# SCH_USB-2_0-KVM-Switch-Hub_2026-04-15.net
KiCad netlist of a schematic drawn in EasyEDA
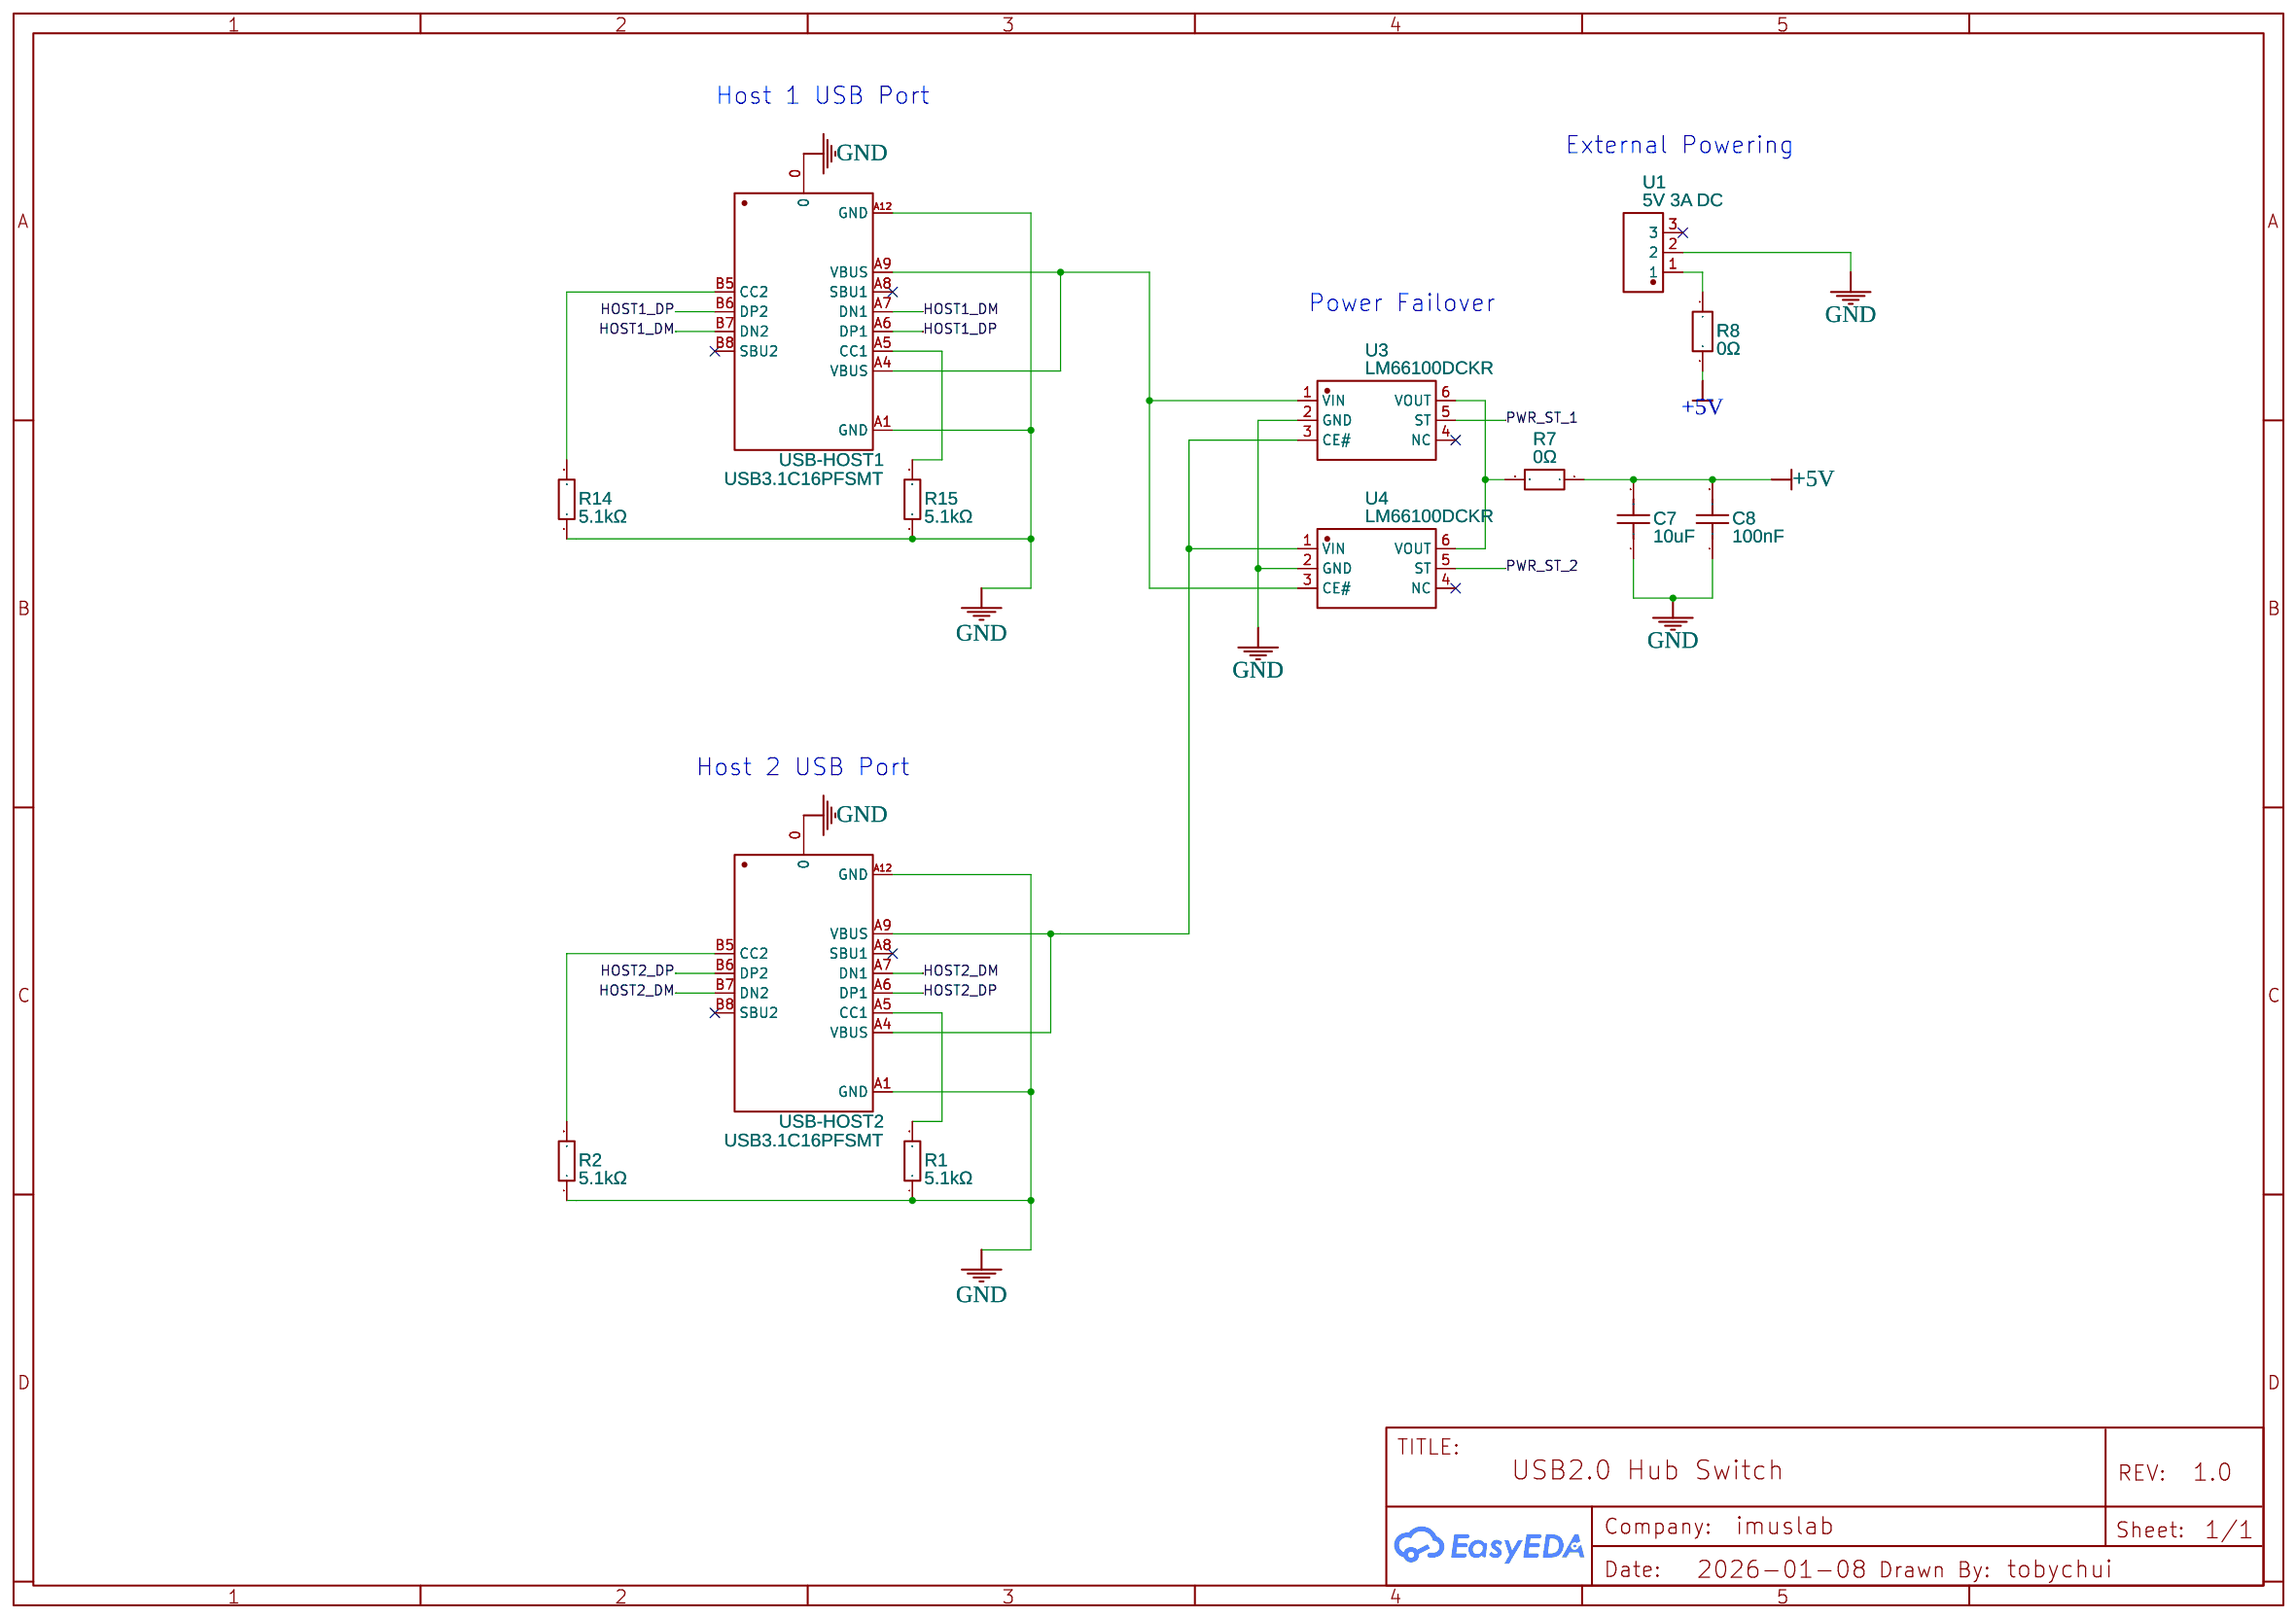
[diagram p0: hosts]
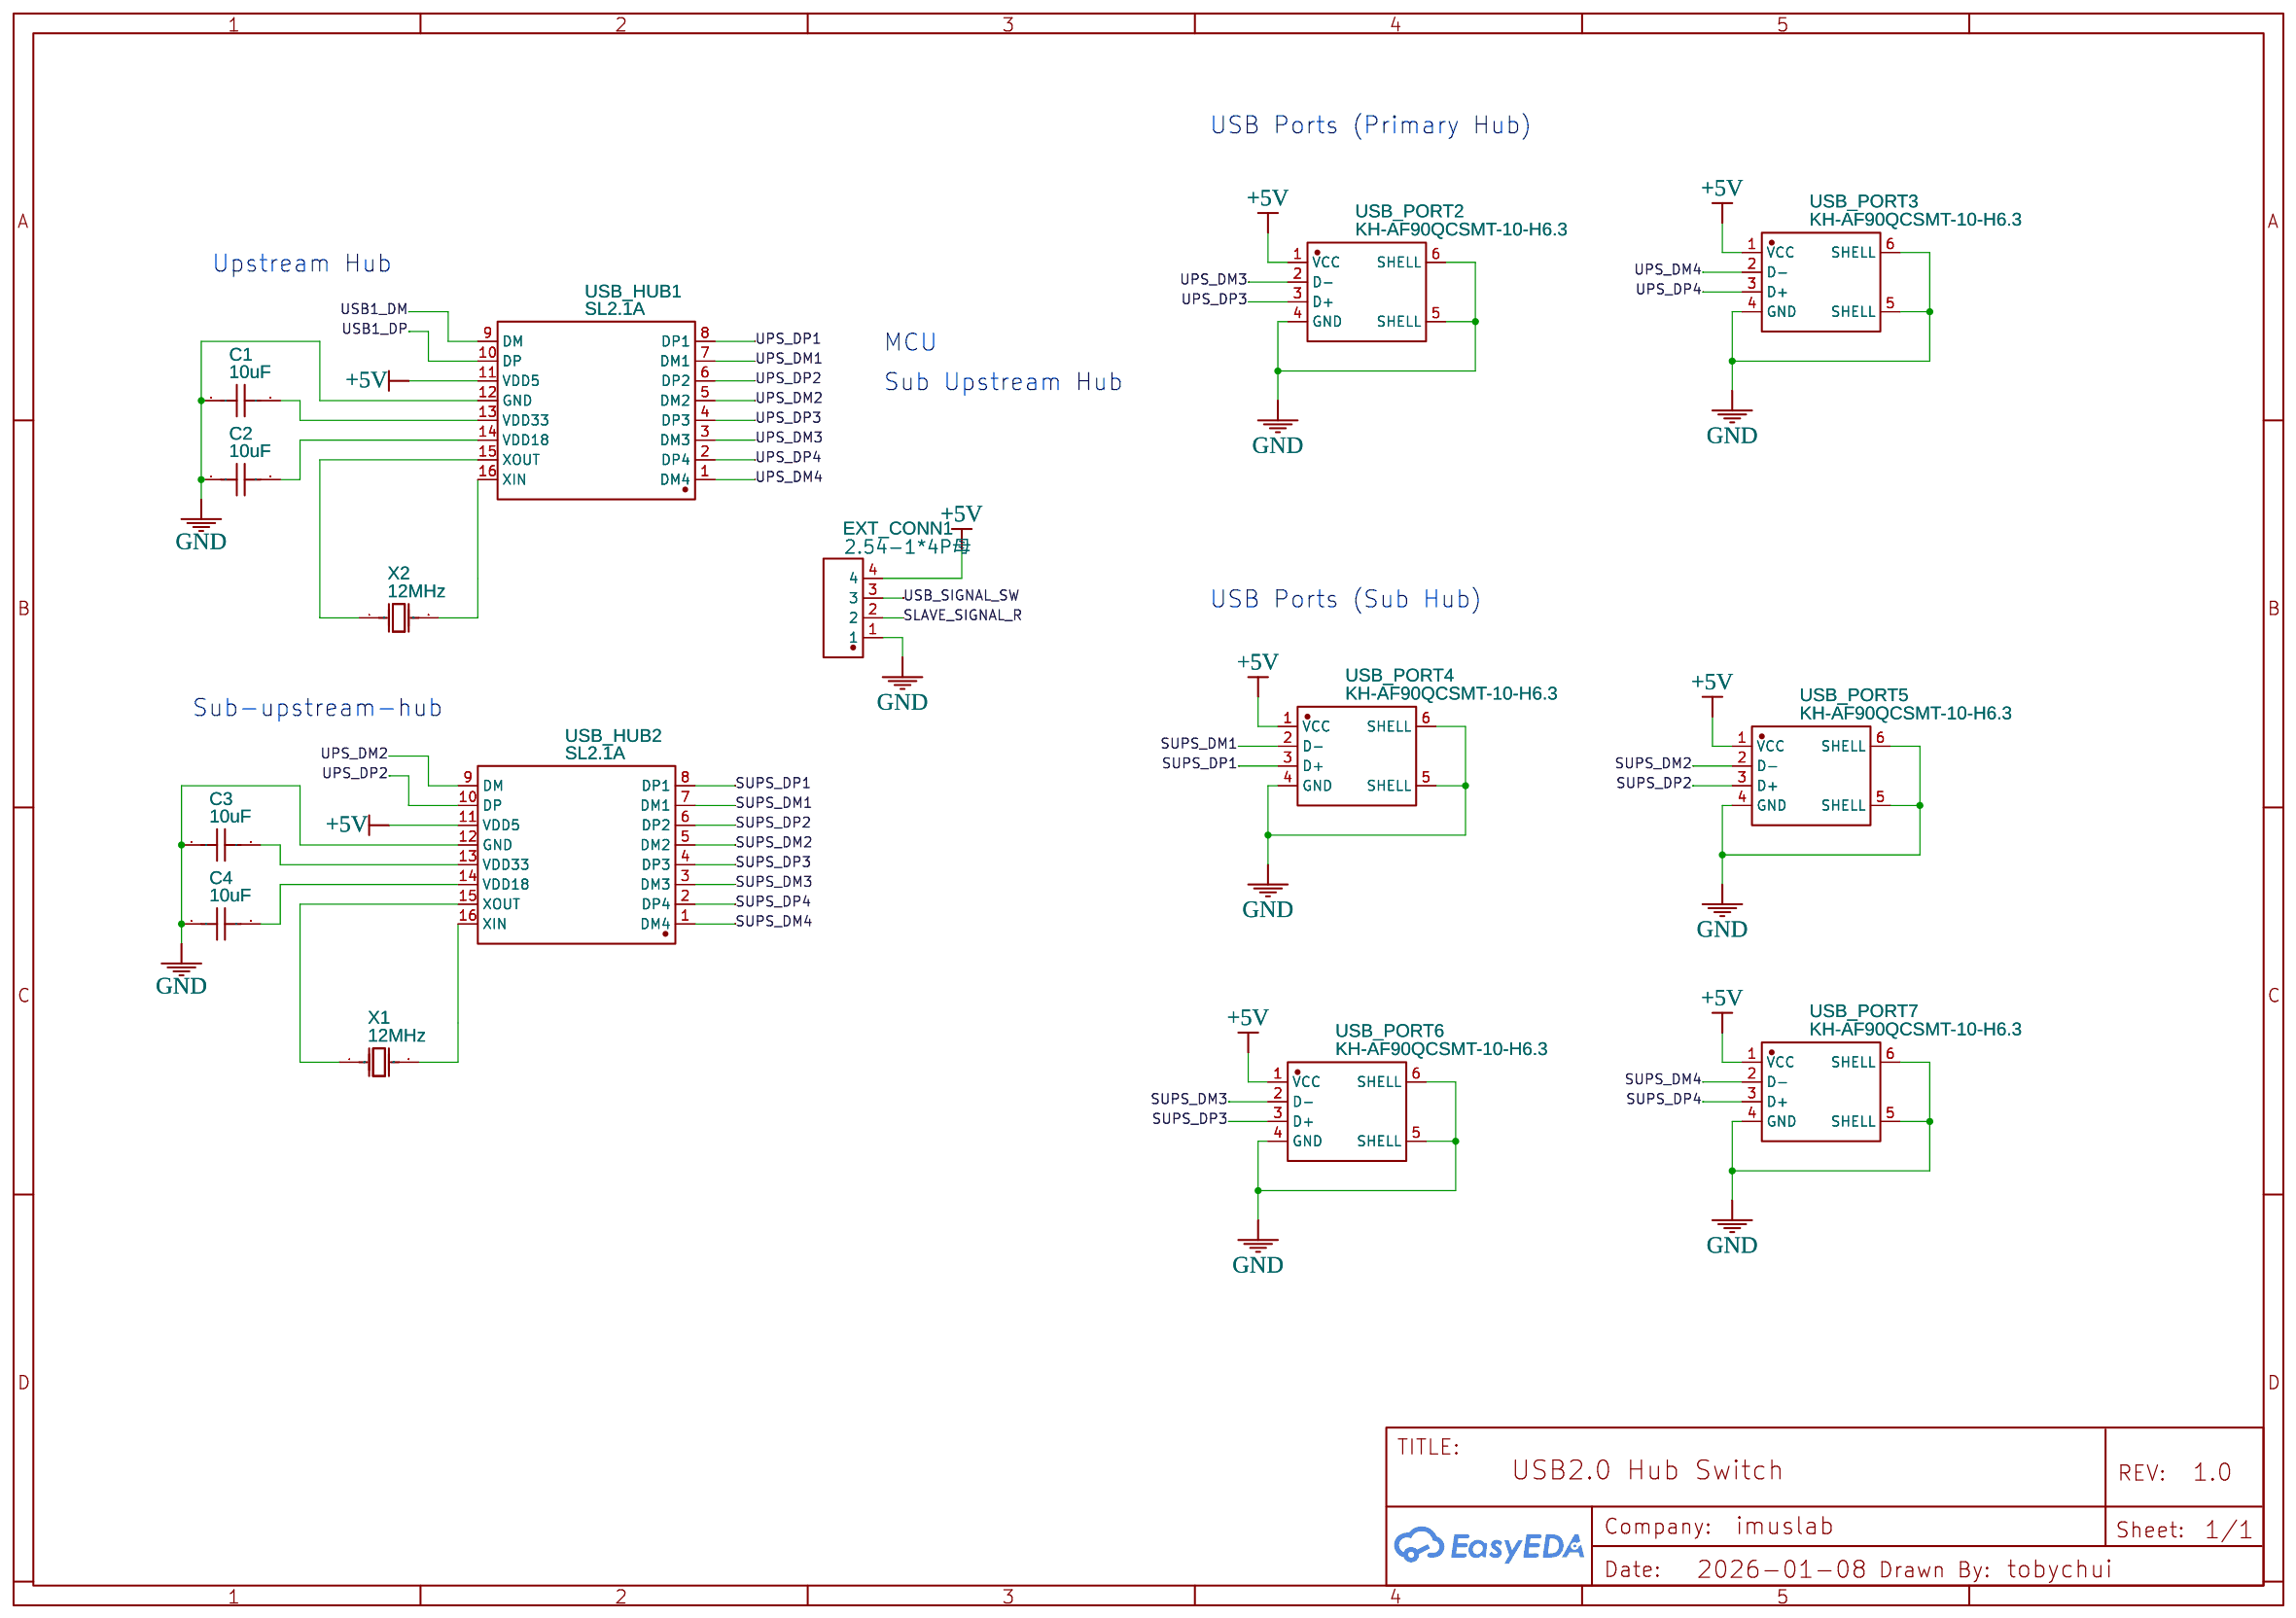
[diagram p1: usb]
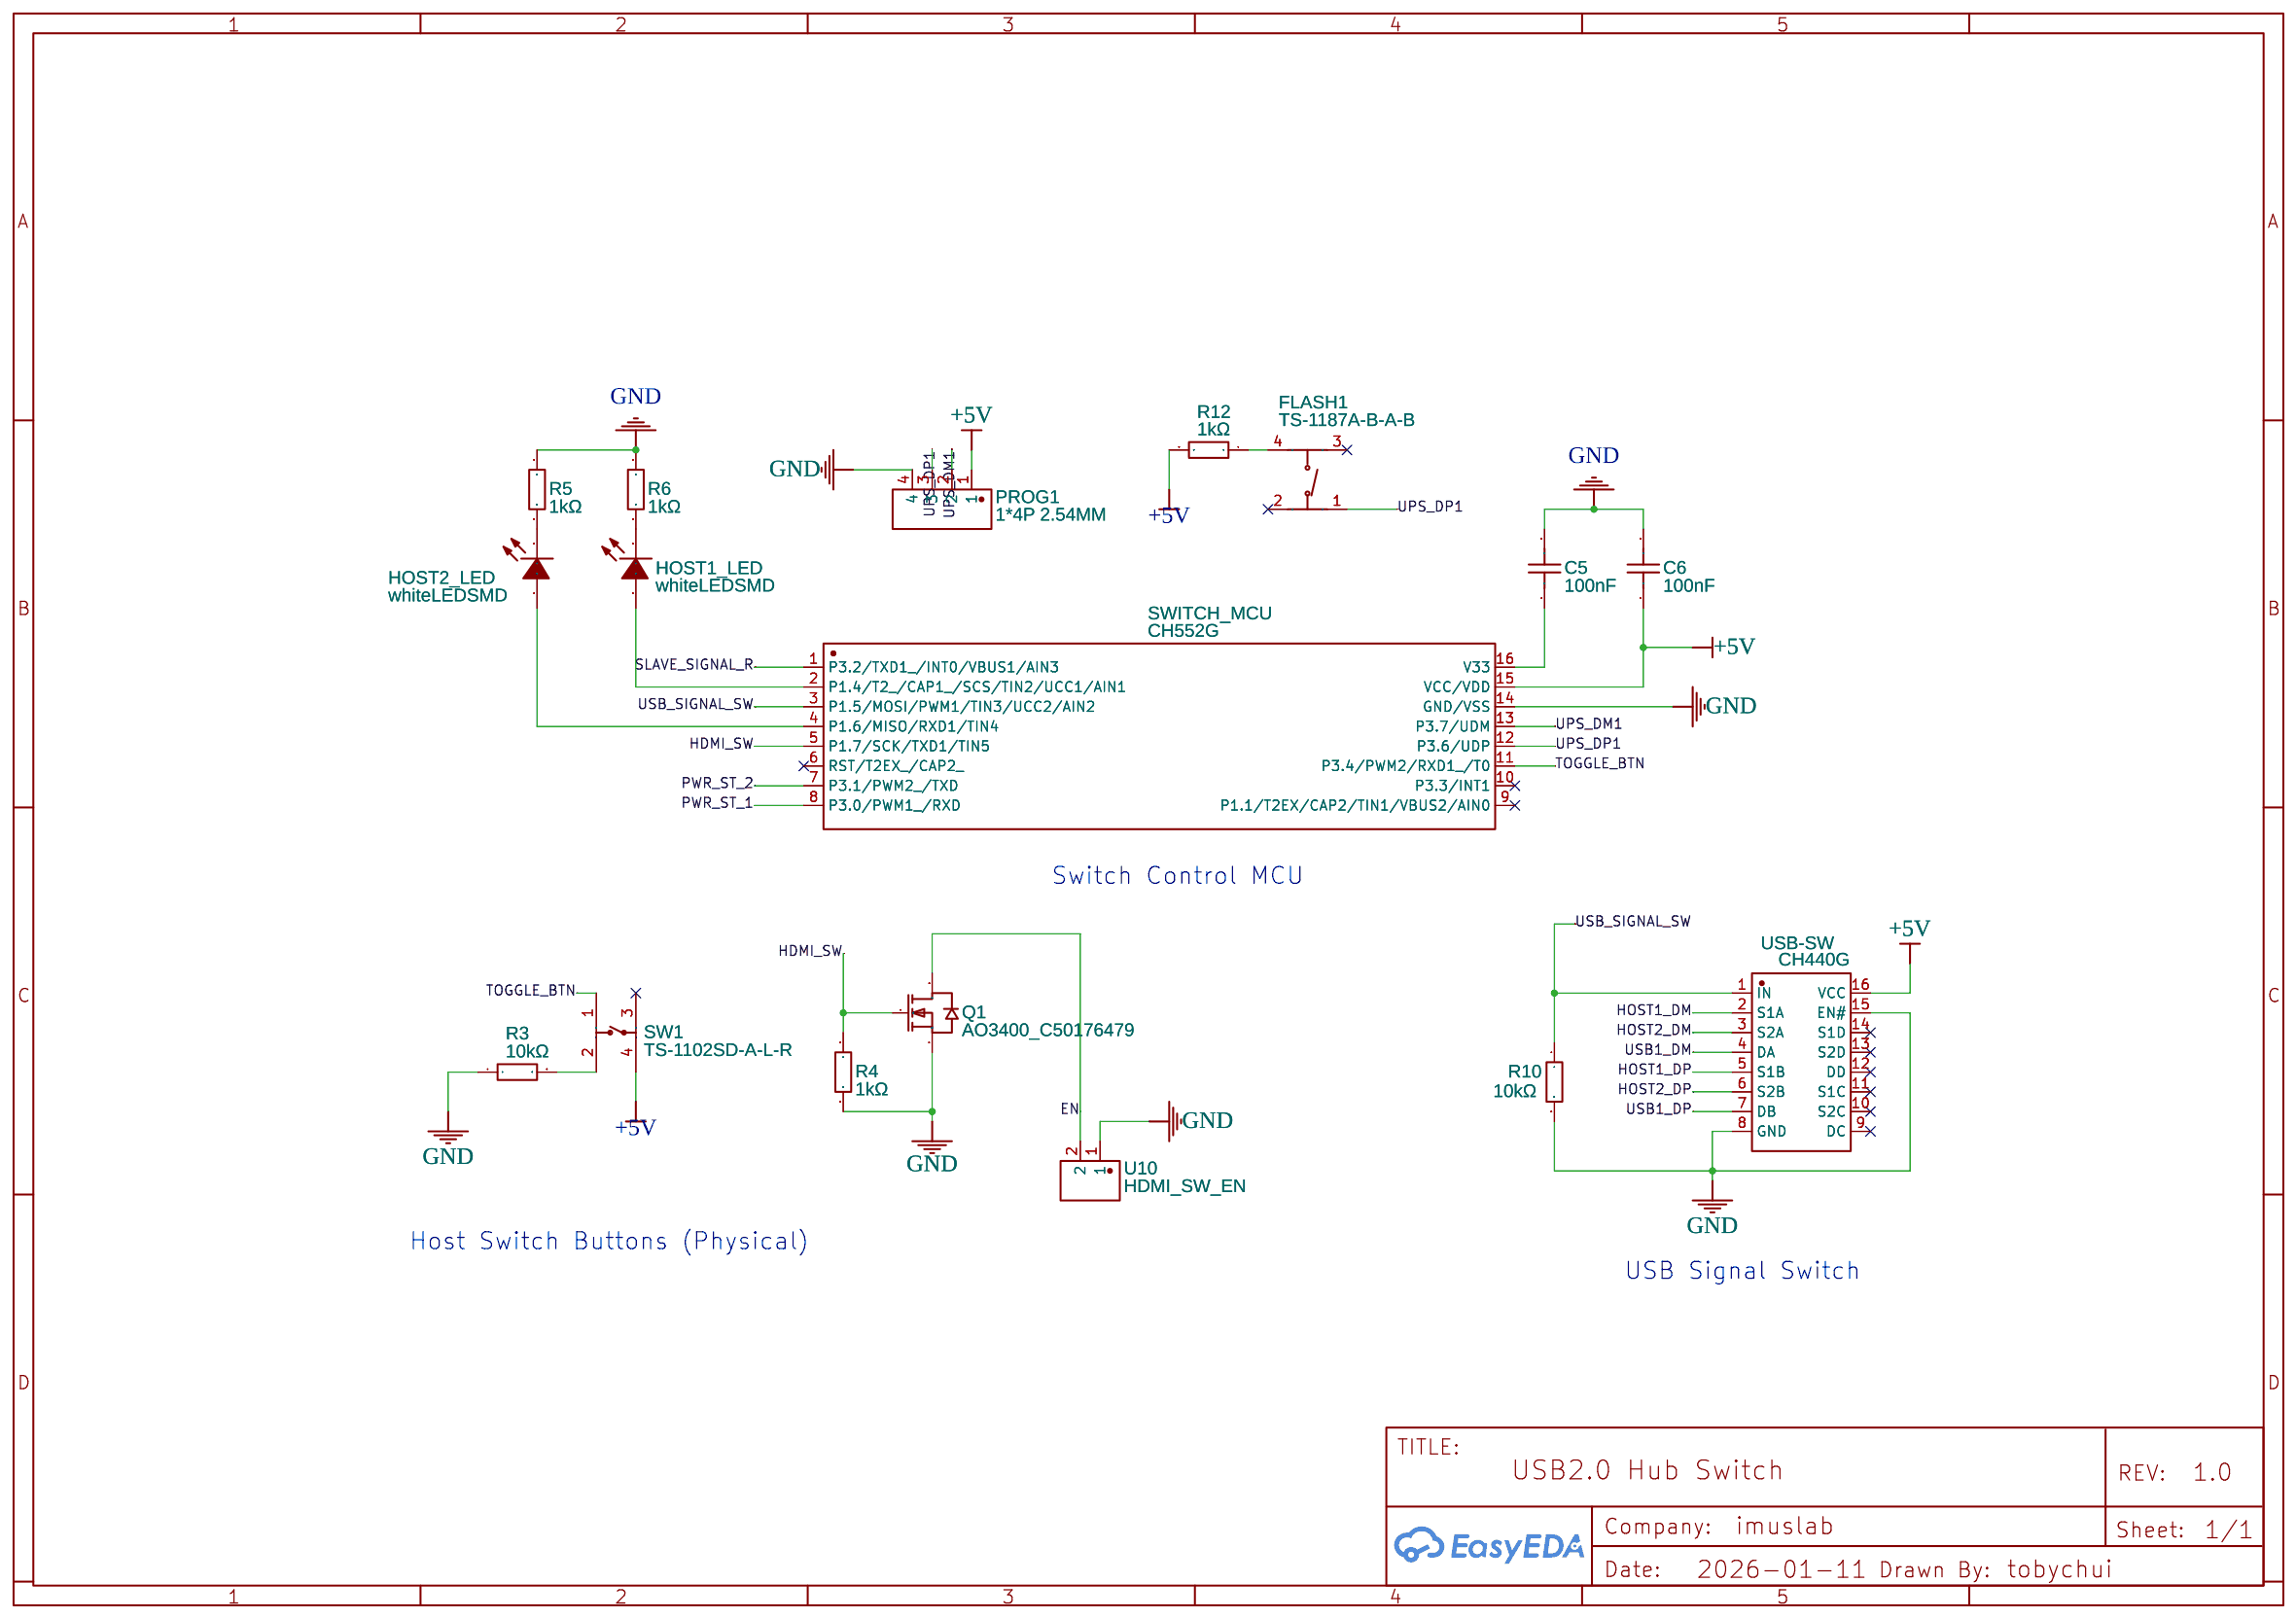
[diagram p2: Switching]

(export (version "E")
  (design (tool "Eeschema 10.0.6"))
  (components
    (comp (ref "C7")
      (value "10uF")
      (fields
        (field (name "Manufacturer Part") "CL21A106KAYNNNE")
        (field (name "Manufacturer") "SAMSUNG(三星)")
      )
      (libsource (lib "") (part "CL21A106KAYNNNE"))
    )
    (comp (ref "C8")
      (value "100nF")
      (fields
        (field (name "Manufacturer Part") "CC0805KRX7R9BB104")
        (field (name "Manufacturer") "YAGEO(国巨)")
      )
      (libsource (lib "") (part "CC0805KRX7R9BB104"))
    )
    (comp (ref "R1")
      (value "5.1kΩ")
      (fields
        (field (name "Manufacturer Part") "0805W8F5101T5E")
        (field (name "Manufacturer") "UNI-ROYAL(厚声)")
      )
      (libsource (lib "") (part "0805W8F5101T5E"))
    )
    (comp (ref "R2")
      (value "5.1kΩ")
      (fields
        (field (name "Manufacturer Part") "0805W8F5101T5E")
        (field (name "Manufacturer") "UNI-ROYAL(厚声)")
      )
      (libsource (lib "") (part "0805W8F5101T5E"))
    )
    (comp (ref "R7")
      (value "0Ω")
      (fields (field (name "Manufacturer Part") "YLRY05-W2-0Z") (field (name "Manufacturer") "yezhan(业展)"))
      (libsource (lib "") (part "YLRY05-W2-0Z_1"))
    )
    (comp (ref "R8")
      (value "0Ω")
      (fields (field (name "Manufacturer Part") "YLRY05-W2-0Z") (field (name "Manufacturer") "yezhan(业展)"))
      (libsource (lib "") (part "YLRY05-W2-0Z"))
    )
    (comp (ref "R14")
      (value "5.1kΩ")
      (fields
        (field (name "Manufacturer Part") "0805W8F5101T5E")
        (field (name "Manufacturer") "UNI-ROYAL(厚声)")
      )
      (libsource (lib "") (part "0805W8F5101T5E"))
    )
    (comp (ref "R15")
      (value "5.1kΩ")
      (fields
        (field (name "Manufacturer Part") "0805W8F5101T5E")
        (field (name "Manufacturer") "UNI-ROYAL(厚声)")
      )
      (libsource (lib "") (part "0805W8F5101T5E"))
    )
    (comp (ref "U1")
      (value "5V 3A DC")
      (fields (field (name "Manufacturer Part") "HC-DC-007B-2.5") (field (name "Manufacturer") "HCTL(华灿天禄)"))
      (libsource (lib "") (part "HC-DC-007B-2.5"))
    )
    (comp (ref "U3")
      (value "LM66100DCKR")
      (fields (field (name "Manufacturer") "TI(德州仪器)"))
      (libsource (lib "") (part "LM66100DCKR"))
    )
    (comp (ref "U4")
      (value "LM66100DCKR")
      (fields (field (name "Manufacturer") "TI(德州仪器)"))
      (libsource (lib "") (part "LM66100DCKR"))
    )
    (comp (ref "USB-HOST1")
      (value "USB3.1C16PFSMT")
      (fields (field (name "Manufacturer Part") "918-418K2023S40001") (field (name "Manufacturer") "精拓金"))
      (libsource (lib "") (part "USB3.1C16PFSMT"))
    )
    (comp (ref "USB-HOST2")
      (value "USB3.1C16PFSMT")
      (fields (field (name "Manufacturer Part") "918-418K2023S40001") (field (name "Manufacturer") "精拓金"))
      (libsource (lib "") (part "USB3.1C16PFSMT"))
    )
    (comp (ref "C1")
      (value "10uF")
      (fields
        (field (name "Manufacturer Part") "CL21A106KAYNNNE")
        (field (name "Manufacturer") "SAMSUNG(三星)")
      )
      (libsource (lib "") (part "CL21A106KAYNNNE"))
    )
    (comp (ref "C2")
      (value "10uF")
      (fields
        (field (name "Manufacturer Part") "CL21A106KAYNNNE")
        (field (name "Manufacturer") "SAMSUNG(三星)")
      )
      (libsource (lib "") (part "CL21A106KAYNNNE"))
    )
    (comp (ref "C3")
      (value "10uF")
      (fields
        (field (name "Manufacturer Part") "CL21A106KAYNNNE")
        (field (name "Manufacturer") "SAMSUNG(三星)")
      )
      (libsource (lib "") (part "CL21A106KAYNNNE"))
    )
    (comp (ref "C4")
      (value "10uF")
      (fields
        (field (name "Manufacturer Part") "CL21A106KAYNNNE")
        (field (name "Manufacturer") "SAMSUNG(三星)")
      )
      (libsource (lib "") (part "CL21A106KAYNNNE"))
    )
    (comp (ref "EXT_CONN1")
      (value "2.54-1*4P母")
      (fields (field (name "Manufacturer") "BOOMELE(博穆精密)"))
      (libsource (lib "") (part "2.54-1*4P母"))
    )
    (comp (ref "USB_HUB1")
      (value "SL2.1A")
      (fields (field (name "Manufacturer") "CoreChips(和芯润德)"))
      (libsource (lib "") (part "SL2.1A"))
    )
    (comp (ref "USB_HUB2")
      (value "SL2.1A")
      (fields (field (name "Manufacturer") "CoreChips(和芯润德)"))
      (libsource (lib "") (part "SL2.1A"))
    )
    (comp (ref "USB_PORT2")
      (value "KH-AF90QCSMT-10-H6.3")
      (fields (field (name "Manufacturer") "kinghelm(金航标)"))
      (libsource (lib "") (part "KH-AF90QCSMT-10-H6.3"))
    )
    (comp (ref "USB_PORT3")
      (value "KH-AF90QCSMT-10-H6.3")
      (fields (field (name "Manufacturer") "kinghelm(金航标)"))
      (libsource (lib "") (part "KH-AF90QCSMT-10-H6.3"))
    )
    (comp (ref "USB_PORT4")
      (value "KH-AF90QCSMT-10-H6.3")
      (fields (field (name "Manufacturer") "kinghelm(金航标)"))
      (libsource (lib "") (part "KH-AF90QCSMT-10-H6.3"))
    )
    (comp (ref "USB_PORT5")
      (value "KH-AF90QCSMT-10-H6.3")
      (fields (field (name "Manufacturer") "kinghelm(金航标)"))
      (libsource (lib "") (part "KH-AF90QCSMT-10-H6.3"))
    )
    (comp (ref "USB_PORT6")
      (value "KH-AF90QCSMT-10-H6.3")
      (fields (field (name "Manufacturer") "kinghelm(金航标)"))
      (libsource (lib "") (part "KH-AF90QCSMT-10-H6.3"))
    )
    (comp (ref "USB_PORT7")
      (value "KH-AF90QCSMT-10-H6.3")
      (fields (field (name "Manufacturer") "kinghelm(金航标)"))
      (libsource (lib "") (part "KH-AF90QCSMT-10-H6.3"))
    )
    (comp (ref "X1")
      (value "12MHz")
      (fields (field (name "Manufacturer Part") "X503212MSD2GI") (field (name "Manufacturer") "YXC(扬兴晶振)"))
      (libsource (lib "") (part "X503212MSD2GI"))
    )
    (comp (ref "X2")
      (value "12MHz")
      (fields (field (name "Manufacturer Part") "X503212MSD2GI") (field (name "Manufacturer") "YXC(扬兴晶振)"))
      (libsource (lib "") (part "X503212MSD2GI"))
    )
    (comp (ref "C5")
      (value "100nF")
      (fields
        (field (name "Manufacturer Part") "CC0805KRX7R9BB104")
        (field (name "Manufacturer") "YAGEO(国巨)")
      )
      (libsource (lib "") (part "CC0805KRX7R9BB104"))
    )
    (comp (ref "C6")
      (value "100nF")
      (fields
        (field (name "Manufacturer Part") "CC0805KRX7R9BB104")
        (field (name "Manufacturer") "YAGEO(国巨)")
      )
      (libsource (lib "") (part "CC0805KRX7R9BB104"))
    )
    (comp (ref "FLASH1")
      (value "TS-1187A-B-A-B")
      (fields (field (name "Manufacturer") "XKB Connectivity(中国星坤)"))
      (libsource (lib "") (part "TS-1187A-B-A-B"))
    )
    (comp (ref "HOST1_LED")
      (value "whiteLEDSMD")
      (fields (field (name "Manufacturer Part") "KT-0805W") (field (name "Manufacturer") "KENTO"))
      (libsource (lib "") (part "whiteLEDSMD"))
    )
    (comp (ref "HOST2_LED")
      (value "whiteLEDSMD")
      (fields (field (name "Manufacturer Part") "KT-0805W") (field (name "Manufacturer") "KENTO"))
      (libsource (lib "") (part "whiteLEDSMD_1"))
    )
    (comp (ref "PROG1")
      (value "1*4P 2.54MM")
      (fields (field (name "Manufacturer Part") "单排直插排针 1*4P 2.54mm"))
      (libsource (lib "") (part "1*4P 2.54MM"))
    )
    (comp (ref "Q1")
      (value "AO3400_C50176479")
      (fields (field (name "Manufacturer Part") "AO3400") (field (name "Manufacturer") "SEP(威旺)"))
      (libsource (lib "") (part "AO3400_C50176479"))
    )
    (comp (ref "R3")
      (value "10kΩ")
      (fields
        (field (name "Manufacturer Part") "0805W8F1002T5E")
        (field (name "Manufacturer") "UNI-ROYAL(厚声)")
      )
      (libsource (lib "") (part "0805W8F1002T5E_1"))
    )
    (comp (ref "R4")
      (value "1kΩ")
      (fields
        (field (name "Manufacturer Part") "0805W8F1001T5E")
        (field (name "Manufacturer") "UNI-ROYAL(厚声)")
      )
      (libsource (lib "") (part "0805W8F1001T5E"))
    )
    (comp (ref "R5")
      (value "1kΩ")
      (fields
        (field (name "Manufacturer Part") "0805W8F1001T5E")
        (field (name "Manufacturer") "UNI-ROYAL(厚声)")
      )
      (libsource (lib "") (part "0805W8F1001T5E"))
    )
    (comp (ref "R6")
      (value "1kΩ")
      (fields
        (field (name "Manufacturer Part") "0805W8F1001T5E")
        (field (name "Manufacturer") "UNI-ROYAL(厚声)")
      )
      (libsource (lib "") (part "0805W8F1001T5E"))
    )
    (comp (ref "R10")
      (value "10kΩ")
      (fields
        (field (name "Manufacturer Part") "0805W8F1002T5E")
        (field (name "Manufacturer") "UNI-ROYAL(厚声)")
      )
      (libsource (lib "") (part "0805W8F1002T5E"))
    )
    (comp (ref "R12")
      (value "1kΩ")
      (fields
        (field (name "Manufacturer Part") "0805W8F1001T5E")
        (field (name "Manufacturer") "UNI-ROYAL(厚声)")
      )
      (libsource (lib "") (part "0805W8F1001T5E_1"))
    )
    (comp (ref "SW1")
      (value "TS-1102SD-A-L-R")
      (fields (field (name "Manufacturer") "XKB Connection(中国星坤)"))
      (libsource (lib "") (part "TS-1102SD-A-L-R"))
    )
    (comp (ref "SWITCH_MCU")
      (value "CH552G")
      (fields (field (name "Manufacturer") "WCH(南京沁恒)"))
      (libsource (lib "") (part "CH552G"))
    )
    (comp (ref "U10")
      (value "HDMI_SW_EN")
      (fields
        (field (name "Manufacturer Part") "254PM-1x2P-V")
        (field (name "Manufacturer") "LXWCONN(连兴旺电子)")
      )
      (libsource (lib "") (part "254PM-1X2P-V"))
    )
    (comp (ref "USB-SW")
      (value "CH440G")
      (fields (field (name "Manufacturer") "WCH(南京沁恒)"))
      (libsource (lib "") (part "CH440G"))
    )
  )
  (nets
    (net (code "1") (name "+5V") (class "Default")
      (node (ref "C6") (pin "1") (pinfunction "1_1") (pintype "unspecified"))
      (node (ref "C7") (pin "2") (pinfunction "2_2") (pintype "unspecified"))
      (node (ref "C8") (pin "2") (pinfunction "2_2") (pintype "unspecified"))
      (node (ref "EXT_CONN1") (pin "4") (pinfunction "4_4") (pintype "unspecified"))
      (node (ref "PROG1") (pin "1") (pinfunction "1_1") (pintype "unspecified"))
      (node (ref "R12") (pin "2") (pinfunction "2_2") (pintype "input"))
      (node (ref "R7") (pin "1") (pinfunction "1_1") (pintype "unspecified"))
      (node (ref "R8") (pin "2") (pinfunction "2_2") (pintype "unspecified"))
      (node (ref "SW1") (pin "4") (pinfunction "4_4") (pintype "unspecified"))
      (node (ref "SWITCH_MCU") (pin "15") (pinfunction "VCC/VDD_15") (pintype "unspecified"))
      (node (ref "USB-SW") (pin "16") (pinfunction "VCC_16") (pintype "unspecified"))
      (node (ref "USB_HUB1") (pin "11") (pinfunction "VDD5_11") (pintype "unspecified"))
      (node (ref "USB_HUB2") (pin "11") (pinfunction "VDD5_11") (pintype "unspecified"))
      (node (ref "USB_PORT2") (pin "1") (pinfunction "VCC_1") (pintype "unspecified"))
      (node (ref "USB_PORT3") (pin "1") (pinfunction "VCC_1") (pintype "unspecified"))
      (node (ref "USB_PORT4") (pin "1") (pinfunction "VCC_1") (pintype "unspecified"))
      (node (ref "USB_PORT5") (pin "1") (pinfunction "VCC_1") (pintype "unspecified"))
      (node (ref "USB_PORT6") (pin "1") (pinfunction "VCC_1") (pintype "unspecified"))
      (node (ref "USB_PORT7") (pin "1") (pinfunction "VCC_1") (pintype "unspecified"))
    )
    (net (code "2") (name "EN") (class "Default")
      (node (ref "Q1") (pin "3") (pinfunction "D_3") (pintype "unspecified"))
      (node (ref "U10") (pin "2") (pinfunction "2_2") (pintype "unspecified"))
    )
    (net (code "3") (name "GND") (class "Default")
      (node (ref "C1") (pin "1") (pinfunction "1_1") (pintype "unspecified"))
      (node (ref "C2") (pin "1") (pinfunction "1_1") (pintype "unspecified"))
      (node (ref "C3") (pin "1") (pinfunction "1_1") (pintype "unspecified"))
      (node (ref "C4") (pin "1") (pinfunction "1_1") (pintype "unspecified"))
      (node (ref "C5") (pin "2") (pinfunction "2_2") (pintype "unspecified"))
      (node (ref "C6") (pin "2") (pinfunction "2_2") (pintype "unspecified"))
      (node (ref "C7") (pin "1") (pinfunction "1_1") (pintype "unspecified"))
      (node (ref "C8") (pin "1") (pinfunction "1_1") (pintype "unspecified"))
      (node (ref "EXT_CONN1") (pin "1") (pinfunction "1_1") (pintype "unspecified"))
      (node (ref "PROG1") (pin "4") (pinfunction "4_4") (pintype "unspecified"))
      (node (ref "Q1") (pin "2") (pinfunction "S_2") (pintype "unspecified"))
      (node (ref "R1") (pin "1") (pinfunction "1_1") (pintype "input"))
      (node (ref "R10") (pin "2") (pinfunction "2_2") (pintype "input"))
      (node (ref "R14") (pin "1") (pinfunction "1_1") (pintype "input"))
      (node (ref "R15") (pin "1") (pinfunction "1_1") (pintype "input"))
      (node (ref "R2") (pin "1") (pinfunction "1_1") (pintype "input"))
      (node (ref "R3") (pin "1") (pinfunction "1_1") (pintype "input"))
      (node (ref "R4") (pin "2") (pinfunction "2_2") (pintype "input"))
      (node (ref "R5") (pin "1") (pinfunction "1_1") (pintype "input"))
      (node (ref "R6") (pin "1") (pinfunction "1_1") (pintype "input"))
      (node (ref "SWITCH_MCU") (pin "14") (pinfunction "GND/VSS_14") (pintype "unspecified"))
      (node (ref "U1") (pin "2") (pinfunction "2_2") (pintype "unspecified"))
      (node (ref "U10") (pin "1") (pinfunction "1_1") (pintype "unspecified"))
      (node (ref "U3") (pin "2") (pinfunction "GND_2") (pintype "unspecified"))
      (node (ref "U4") (pin "2") (pinfunction "GND_2") (pintype "unspecified"))
      (node (ref "USB-HOST1") (pin "0") (pinfunction "0_0") (pintype "unspecified"))
      (node (ref "USB-HOST1") (pin "A1") (pinfunction "GND_A1") (pintype "unspecified"))
      (node (ref "USB-HOST1") (pin "A12") (pinfunction "GND_A12") (pintype "unspecified"))
      (node (ref "USB-HOST2") (pin "0") (pinfunction "0_0") (pintype "unspecified"))
      (node (ref "USB-HOST2") (pin "A1") (pinfunction "GND_A1") (pintype "unspecified"))
      (node (ref "USB-HOST2") (pin "A12") (pinfunction "GND_A12") (pintype "unspecified"))
      (node (ref "USB-SW") (pin "15") (pinfunction "EN#_15") (pintype "unspecified"))
      (node (ref "USB-SW") (pin "8") (pinfunction "GND_8") (pintype "unspecified"))
      (node (ref "USB_HUB1") (pin "12") (pinfunction "GND_12") (pintype "unspecified"))
      (node (ref "USB_HUB2") (pin "12") (pinfunction "GND_12") (pintype "unspecified"))
      (node (ref "USB_PORT2") (pin "4") (pinfunction "GND_4") (pintype "unspecified"))
      (node (ref "USB_PORT2") (pin "5") (pinfunction "SHELL_5") (pintype "unspecified"))
      (node (ref "USB_PORT2") (pin "6") (pinfunction "SHELL_6") (pintype "unspecified"))
      (node (ref "USB_PORT3") (pin "4") (pinfunction "GND_4") (pintype "unspecified"))
      (node (ref "USB_PORT3") (pin "5") (pinfunction "SHELL_5") (pintype "unspecified"))
      (node (ref "USB_PORT3") (pin "6") (pinfunction "SHELL_6") (pintype "unspecified"))
      (node (ref "USB_PORT4") (pin "4") (pinfunction "GND_4") (pintype "unspecified"))
      (node (ref "USB_PORT4") (pin "5") (pinfunction "SHELL_5") (pintype "unspecified"))
      (node (ref "USB_PORT4") (pin "6") (pinfunction "SHELL_6") (pintype "unspecified"))
      (node (ref "USB_PORT5") (pin "4") (pinfunction "GND_4") (pintype "unspecified"))
      (node (ref "USB_PORT5") (pin "5") (pinfunction "SHELL_5") (pintype "unspecified"))
      (node (ref "USB_PORT5") (pin "6") (pinfunction "SHELL_6") (pintype "unspecified"))
      (node (ref "USB_PORT6") (pin "4") (pinfunction "GND_4") (pintype "unspecified"))
      (node (ref "USB_PORT6") (pin "5") (pinfunction "SHELL_5") (pintype "unspecified"))
      (node (ref "USB_PORT6") (pin "6") (pinfunction "SHELL_6") (pintype "unspecified"))
      (node (ref "USB_PORT7") (pin "4") (pinfunction "GND_4") (pintype "unspecified"))
      (node (ref "USB_PORT7") (pin "5") (pinfunction "SHELL_5") (pintype "unspecified"))
      (node (ref "USB_PORT7") (pin "6") (pinfunction "SHELL_6") (pintype "unspecified"))
    )
    (net (code "4") (name "HDMI_SW") (class "Default")
      (node (ref "Q1") (pin "1") (pinfunction "G_1") (pintype "unspecified"))
      (node (ref "R4") (pin "1") (pinfunction "1_1") (pintype "input"))
      (node (ref "SWITCH_MCU") (pin "5") (pinfunction "P1.7/SCK/TXD1/TIN5_5") (pintype "unspecified"))
    )
    (net (code "5") (name "HOST1_DM") (class "Default")
      (node (ref "USB-HOST1") (pin "A7") (pinfunction "DN1_A7") (pintype "unspecified"))
      (node (ref "USB-HOST1") (pin "B7") (pinfunction "DN2_B7") (pintype "unspecified"))
      (node (ref "USB-SW") (pin "2") (pinfunction "S1A_2") (pintype "unspecified"))
    )
    (net (code "6") (name "HOST1_DP") (class "Default")
      (node (ref "USB-HOST1") (pin "A6") (pinfunction "DP1_A6") (pintype "unspecified"))
      (node (ref "USB-HOST1") (pin "B6") (pinfunction "DP2_B6") (pintype "unspecified"))
      (node (ref "USB-SW") (pin "5") (pinfunction "S1B_5") (pintype "unspecified"))
    )
    (net (code "7") (name "HOST2_DM") (class "Default")
      (node (ref "USB-HOST2") (pin "A7") (pinfunction "DN1_A7") (pintype "unspecified"))
      (node (ref "USB-HOST2") (pin "B7") (pinfunction "DN2_B7") (pintype "unspecified"))
      (node (ref "USB-SW") (pin "3") (pinfunction "S2A_3") (pintype "unspecified"))
    )
    (net (code "8") (name "HOST2_DP") (class "Default")
      (node (ref "USB-HOST2") (pin "A6") (pinfunction "DP1_A6") (pintype "unspecified"))
      (node (ref "USB-HOST2") (pin "B6") (pinfunction "DP2_B6") (pintype "unspecified"))
      (node (ref "USB-SW") (pin "6") (pinfunction "S2B_6") (pintype "unspecified"))
    )
    (net (code "9") (name "Net-(FLASH1-D)") (class "Default")
      (node (ref "FLASH1") (pin "4") (pinfunction "D_4") (pintype "unspecified"))
      (node (ref "R12") (pin "1") (pinfunction "1_1") (pintype "input"))
    )
    (net (code "10") (name "Net-(HOST1_LED-A)") (class "Default")
      (node (ref "HOST1_LED") (pin "1") (pinfunction "A_1") (pintype "unspecified"))
      (node (ref "SWITCH_MCU") (pin "2") (pinfunction "P1.4/T2_/CAP1_/SCS/TIN2/UCC1/AIN1_2") (pintype "unspecified"))
    )
    (net (code "11") (name "Net-(HOST1_LED-K)") (class "Default")
      (node (ref "HOST1_LED") (pin "2") (pinfunction "K_2") (pintype "unspecified"))
      (node (ref "R6") (pin "2") (pinfunction "2_2") (pintype "input"))
    )
    (net (code "12") (name "Net-(HOST2_LED-A)") (class "Default")
      (node (ref "HOST2_LED") (pin "1") (pinfunction "A_1") (pintype "unspecified"))
      (node (ref "SWITCH_MCU") (pin "4") (pinfunction "P1.6/MISO/RXD1/TIN4_4") (pintype "unspecified"))
    )
    (net (code "13") (name "Net-(HOST2_LED-K)") (class "Default")
      (node (ref "HOST2_LED") (pin "2") (pinfunction "K_2") (pintype "unspecified"))
      (node (ref "R5") (pin "2") (pinfunction "2_2") (pintype "input"))
    )
    (net (code "14") (name "Net-(R3-Pad2)") (class "Default")
      (node (ref "R3") (pin "2") (pinfunction "2_2") (pintype "input"))
      (node (ref "SW1") (pin "2") (pinfunction "2_2") (pintype "unspecified"))
    )
    (net (code "15") (name "Net-(R8-Pad1)") (class "Default")
      (node (ref "R8") (pin "1") (pinfunction "1_1") (pintype "unspecified"))
      (node (ref "U1") (pin "1") (pinfunction "1_1") (pintype "unspecified"))
    )
    (net (code "16") (name "Net-(SWITCH_MCU-V33)") (class "Default")
      (node (ref "C5") (pin "1") (pinfunction "1_1") (pintype "unspecified"))
      (node (ref "SWITCH_MCU") (pin "16") (pinfunction "V33_16") (pintype "unspecified"))
    )
    (net (code "17") (name "Net-(U3-CE#)") (class "Default")
      (node (ref "U3") (pin "3") (pinfunction "CE#_3") (pintype "unspecified"))
      (node (ref "U4") (pin "1") (pinfunction "VIN_1") (pintype "unspecified"))
      (node (ref "USB-HOST2") (pin "A4") (pinfunction "VBUS_A4") (pintype "unspecified"))
      (node (ref "USB-HOST2") (pin "A9") (pinfunction "VBUS_A9") (pintype "unspecified"))
    )
    (net (code "18") (name "Net-(U3-VIN)") (class "Default")
      (node (ref "U3") (pin "1") (pinfunction "VIN_1") (pintype "unspecified"))
      (node (ref "U4") (pin "3") (pinfunction "CE#_3") (pintype "unspecified"))
      (node (ref "USB-HOST1") (pin "A4") (pinfunction "VBUS_A4") (pintype "unspecified"))
      (node (ref "USB-HOST1") (pin "A9") (pinfunction "VBUS_A9") (pintype "unspecified"))
    )
    (net (code "19") (name "Net-(U3-VOUT)") (class "Default")
      (node (ref "R7") (pin "2") (pinfunction "2_2") (pintype "unspecified"))
      (node (ref "U3") (pin "6") (pinfunction "VOUT_6") (pintype "unspecified"))
      (node (ref "U4") (pin "6") (pinfunction "VOUT_6") (pintype "unspecified"))
    )
    (net (code "20") (name "Net-(USB-HOST1-CC1)") (class "Default")
      (node (ref "R15") (pin "2") (pinfunction "2_2") (pintype "input"))
      (node (ref "USB-HOST1") (pin "A5") (pinfunction "CC1_A5") (pintype "unspecified"))
    )
    (net (code "21") (name "Net-(USB-HOST1-CC2)") (class "Default")
      (node (ref "R14") (pin "2") (pinfunction "2_2") (pintype "input"))
      (node (ref "USB-HOST1") (pin "B5") (pinfunction "CC2_B5") (pintype "unspecified"))
    )
    (net (code "22") (name "Net-(USB-HOST2-CC1)") (class "Default")
      (node (ref "R1") (pin "2") (pinfunction "2_2") (pintype "input"))
      (node (ref "USB-HOST2") (pin "A5") (pinfunction "CC1_A5") (pintype "unspecified"))
    )
    (net (code "23") (name "Net-(USB-HOST2-CC2)") (class "Default")
      (node (ref "R2") (pin "2") (pinfunction "2_2") (pintype "input"))
      (node (ref "USB-HOST2") (pin "B5") (pinfunction "CC2_B5") (pintype "unspecified"))
    )
    (net (code "24") (name "Net-(USB_HUB1-VDD18)") (class "Default")
      (node (ref "C2") (pin "2") (pinfunction "2_2") (pintype "unspecified"))
      (node (ref "USB_HUB1") (pin "14") (pinfunction "VDD18_14") (pintype "unspecified"))
    )
    (net (code "25") (name "Net-(USB_HUB1-VDD33)") (class "Default")
      (node (ref "C1") (pin "2") (pinfunction "2_2") (pintype "unspecified"))
      (node (ref "USB_HUB1") (pin "13") (pinfunction "VDD33_13") (pintype "unspecified"))
    )
    (net (code "26") (name "Net-(USB_HUB1-XIN)") (class "Default")
      (node (ref "USB_HUB1") (pin "16") (pinfunction "XIN_16") (pintype "unspecified"))
      (node (ref "X2") (pin "2") (pinfunction "OSC2_2") (pintype "input"))
    )
    (net (code "27") (name "Net-(USB_HUB1-XOUT)") (class "Default")
      (node (ref "USB_HUB1") (pin "15") (pinfunction "XOUT_15") (pintype "unspecified"))
      (node (ref "X2") (pin "1") (pinfunction "OSC1_1") (pintype "input"))
    )
    (net (code "28") (name "Net-(USB_HUB2-VDD18)") (class "Default")
      (node (ref "C4") (pin "2") (pinfunction "2_2") (pintype "unspecified"))
      (node (ref "USB_HUB2") (pin "14") (pinfunction "VDD18_14") (pintype "unspecified"))
    )
    (net (code "29") (name "Net-(USB_HUB2-VDD33)") (class "Default")
      (node (ref "C3") (pin "2") (pinfunction "2_2") (pintype "unspecified"))
      (node (ref "USB_HUB2") (pin "13") (pinfunction "VDD33_13") (pintype "unspecified"))
    )
    (net (code "30") (name "Net-(USB_HUB2-XIN)") (class "Default")
      (node (ref "USB_HUB2") (pin "16") (pinfunction "XIN_16") (pintype "unspecified"))
      (node (ref "X1") (pin "2") (pinfunction "OSC2_2") (pintype "input"))
    )
    (net (code "31") (name "Net-(USB_HUB2-XOUT)") (class "Default")
      (node (ref "USB_HUB2") (pin "15") (pinfunction "XOUT_15") (pintype "unspecified"))
      (node (ref "X1") (pin "1") (pinfunction "OSC1_1") (pintype "input"))
    )
    (net (code "32") (name "PWR_ST_1") (class "Default")
      (node (ref "SWITCH_MCU") (pin "8") (pinfunction "P3.0/PWM1_/RXD_8") (pintype "unspecified"))
      (node (ref "U3") (pin "5") (pinfunction "ST_5") (pintype "unspecified"))
    )
    (net (code "33") (name "PWR_ST_2") (class "Default")
      (node (ref "SWITCH_MCU") (pin "7") (pinfunction "P3.1/PWM2_/TXD_7") (pintype "unspecified"))
      (node (ref "U4") (pin "5") (pinfunction "ST_5") (pintype "unspecified"))
    )
    (net (code "34") (name "SLAVE_SIGNAL_R") (class "Default")
      (node (ref "EXT_CONN1") (pin "2") (pinfunction "2_2") (pintype "unspecified"))
      (node (ref "SWITCH_MCU") (pin "1") (pinfunction "P3.2/TXD1_/INT0/VBUS1/AIN3_1") (pintype "unspecified"))
    )
    (net (code "35") (name "SUPS_DM1") (class "Default")
      (node (ref "USB_HUB2") (pin "7") (pinfunction "DM1_7") (pintype "unspecified"))
      (node (ref "USB_PORT4") (pin "2") (pinfunction "D-_2") (pintype "unspecified"))
    )
    (net (code "36") (name "SUPS_DM2") (class "Default")
      (node (ref "USB_HUB2") (pin "5") (pinfunction "DM2_5") (pintype "unspecified"))
      (node (ref "USB_PORT5") (pin "2") (pinfunction "D-_2") (pintype "unspecified"))
    )
    (net (code "37") (name "SUPS_DM3") (class "Default")
      (node (ref "USB_HUB2") (pin "3") (pinfunction "DM3_3") (pintype "unspecified"))
      (node (ref "USB_PORT6") (pin "2") (pinfunction "D-_2") (pintype "unspecified"))
    )
    (net (code "38") (name "SUPS_DM4") (class "Default")
      (node (ref "USB_HUB2") (pin "1") (pinfunction "DM4_1") (pintype "unspecified"))
      (node (ref "USB_PORT7") (pin "2") (pinfunction "D-_2") (pintype "unspecified"))
    )
    (net (code "39") (name "SUPS_DP1") (class "Default")
      (node (ref "USB_HUB2") (pin "8") (pinfunction "DP1_8") (pintype "unspecified"))
      (node (ref "USB_PORT4") (pin "3") (pinfunction "D+_3") (pintype "unspecified"))
    )
    (net (code "40") (name "SUPS_DP2") (class "Default")
      (node (ref "USB_HUB2") (pin "6") (pinfunction "DP2_6") (pintype "unspecified"))
      (node (ref "USB_PORT5") (pin "3") (pinfunction "D+_3") (pintype "unspecified"))
    )
    (net (code "41") (name "SUPS_DP3") (class "Default")
      (node (ref "USB_HUB2") (pin "4") (pinfunction "DP3_4") (pintype "unspecified"))
      (node (ref "USB_PORT6") (pin "3") (pinfunction "D+_3") (pintype "unspecified"))
    )
    (net (code "42") (name "SUPS_DP4") (class "Default")
      (node (ref "USB_HUB2") (pin "2") (pinfunction "DP4_2") (pintype "unspecified"))
      (node (ref "USB_PORT7") (pin "3") (pinfunction "D+_3") (pintype "unspecified"))
    )
    (net (code "43") (name "TOGGLE_BTN") (class "Default")
      (node (ref "SW1") (pin "1") (pinfunction "1_1") (pintype "unspecified"))
      (node (ref "SWITCH_MCU") (pin "11") (pinfunction "P3.4/PWM2/RXD1_/T0_11") (pintype "unspecified"))
    )
    (net (code "44") (name "UPS_DM1") (class "Default")
      (node (ref "PROG1") (pin "2") (pinfunction "2_2") (pintype "unspecified"))
      (node (ref "SWITCH_MCU") (pin "13") (pinfunction "P3.7/UDM_13") (pintype "unspecified"))
      (node (ref "USB_HUB1") (pin "7") (pinfunction "DM1_7") (pintype "unspecified"))
    )
    (net (code "45") (name "UPS_DM2") (class "Default")
      (node (ref "USB_HUB1") (pin "5") (pinfunction "DM2_5") (pintype "unspecified"))
      (node (ref "USB_HUB2") (pin "9") (pinfunction "DM_9") (pintype "unspecified"))
    )
    (net (code "46") (name "UPS_DM3") (class "Default")
      (node (ref "USB_HUB1") (pin "3") (pinfunction "DM3_3") (pintype "unspecified"))
      (node (ref "USB_PORT2") (pin "2") (pinfunction "D-_2") (pintype "unspecified"))
    )
    (net (code "47") (name "UPS_DM4") (class "Default")
      (node (ref "USB_HUB1") (pin "1") (pinfunction "DM4_1") (pintype "unspecified"))
      (node (ref "USB_PORT3") (pin "2") (pinfunction "D-_2") (pintype "unspecified"))
    )
    (net (code "48") (name "UPS_DP1") (class "Default")
      (node (ref "FLASH1") (pin "1") (pinfunction "A_1") (pintype "unspecified"))
      (node (ref "PROG1") (pin "3") (pinfunction "3_3") (pintype "unspecified"))
      (node (ref "SWITCH_MCU") (pin "12") (pinfunction "P3.6/UDP_12") (pintype "unspecified"))
      (node (ref "USB_HUB1") (pin "8") (pinfunction "DP1_8") (pintype "unspecified"))
    )
    (net (code "49") (name "UPS_DP2") (class "Default")
      (node (ref "USB_HUB1") (pin "6") (pinfunction "DP2_6") (pintype "unspecified"))
      (node (ref "USB_HUB2") (pin "10") (pinfunction "DP_10") (pintype "unspecified"))
    )
    (net (code "50") (name "UPS_DP3") (class "Default")
      (node (ref "USB_HUB1") (pin "4") (pinfunction "DP3_4") (pintype "unspecified"))
      (node (ref "USB_PORT2") (pin "3") (pinfunction "D+_3") (pintype "unspecified"))
    )
    (net (code "51") (name "UPS_DP4") (class "Default")
      (node (ref "USB_HUB1") (pin "2") (pinfunction "DP4_2") (pintype "unspecified"))
      (node (ref "USB_PORT3") (pin "3") (pinfunction "D+_3") (pintype "unspecified"))
    )
    (net (code "52") (name "USB1_DM") (class "Default")
      (node (ref "USB-SW") (pin "4") (pinfunction "DA_4") (pintype "unspecified"))
      (node (ref "USB_HUB1") (pin "9") (pinfunction "DM_9") (pintype "unspecified"))
    )
    (net (code "53") (name "USB1_DP") (class "Default")
      (node (ref "USB-SW") (pin "7") (pinfunction "DB_7") (pintype "unspecified"))
      (node (ref "USB_HUB1") (pin "10") (pinfunction "DP_10") (pintype "unspecified"))
    )
    (net (code "54") (name "USB_SIGNAL_SW") (class "Default")
      (node (ref "EXT_CONN1") (pin "3") (pinfunction "3_3") (pintype "unspecified"))
      (node (ref "R10") (pin "1") (pinfunction "1_1") (pintype "input"))
      (node (ref "SWITCH_MCU") (pin "3") (pinfunction "P1.5/MOSI/PWM1/TIN3/UCC2/AIN2_3") (pintype "unspecified"))
      (node (ref "USB-SW") (pin "1") (pinfunction "IN_1") (pintype "unspecified"))
    )
    (net (code "55") (name "unconnected-(FLASH1-B-Pad2)") (class "Default")
      (node (ref "FLASH1") (pin "2") (pinfunction "B_2") (pintype "unspecified+no_connect"))
    )
    (net (code "56") (name "unconnected-(FLASH1-C-Pad3)") (class "Default")
      (node (ref "FLASH1") (pin "3") (pinfunction "C_3") (pintype "unspecified+no_connect"))
    )
    (net (code "57") (name "unconnected-(SW1-Pad3)") (class "Default")
      (node (ref "SW1") (pin "3") (pinfunction "3_3") (pintype "unspecified+no_connect"))
    )
    (net (code "58") (name "unconnected-(SWITCH_MCU-P1.1{slash}T2EX{slash}CAP2{slash}TIN1{slash}VBUS2{slash}AIN0-Pad9)") (class "Default")
      (node (ref "SWITCH_MCU") (pin "9") (pinfunction "P1.1/T2EX/CAP2/TIN1/VBUS2/AIN0_9") (pintype "unspecified+no_connect"))
    )
    (net (code "59") (name "unconnected-(SWITCH_MCU-P3.3{slash}INT1-Pad10)") (class "Default")
      (node (ref "SWITCH_MCU") (pin "10") (pinfunction "P3.3/INT1_10") (pintype "unspecified+no_connect"))
    )
    (net (code "60") (name "unconnected-(SWITCH_MCU-RST{slash}T2EX_{slash}CAP2_-Pad6)") (class "Default")
      (node (ref "SWITCH_MCU") (pin "6") (pinfunction "RST/T2EX_/CAP2__6") (pintype "unspecified+no_connect"))
    )
    (net (code "61") (name "unconnected-(U1-Pad3)") (class "Default")
      (node (ref "U1") (pin "3") (pinfunction "3_3") (pintype "unspecified+no_connect"))
    )
    (net (code "62") (name "unconnected-(U3-NC-Pad4)") (class "Default")
      (node (ref "U3") (pin "4") (pinfunction "NC_4") (pintype "unspecified+no_connect"))
    )
    (net (code "63") (name "unconnected-(U4-NC-Pad4)") (class "Default")
      (node (ref "U4") (pin "4") (pinfunction "NC_4") (pintype "unspecified+no_connect"))
    )
    (net (code "64") (name "unconnected-(USB-HOST1-SBU1-PadA8)") (class "Default")
      (node (ref "USB-HOST1") (pin "A8") (pinfunction "SBU1_A8") (pintype "unspecified+no_connect"))
    )
    (net (code "65") (name "unconnected-(USB-HOST1-SBU2-PadB8)") (class "Default")
      (node (ref "USB-HOST1") (pin "B8") (pinfunction "SBU2_B8") (pintype "unspecified+no_connect"))
    )
    (net (code "66") (name "unconnected-(USB-HOST2-SBU1-PadA8)") (class "Default")
      (node (ref "USB-HOST2") (pin "A8") (pinfunction "SBU1_A8") (pintype "unspecified+no_connect"))
    )
    (net (code "67") (name "unconnected-(USB-HOST2-SBU2-PadB8)") (class "Default")
      (node (ref "USB-HOST2") (pin "B8") (pinfunction "SBU2_B8") (pintype "unspecified+no_connect"))
    )
    (net (code "68") (name "unconnected-(USB-SW-DC-Pad9)") (class "Default")
      (node (ref "USB-SW") (pin "9") (pinfunction "DC_9") (pintype "unspecified+no_connect"))
    )
    (net (code "69") (name "unconnected-(USB-SW-DD-Pad12)") (class "Default")
      (node (ref "USB-SW") (pin "12") (pinfunction "DD_12") (pintype "unspecified+no_connect"))
    )
    (net (code "70") (name "unconnected-(USB-SW-S1C-Pad11)") (class "Default")
      (node (ref "USB-SW") (pin "11") (pinfunction "S1C_11") (pintype "unspecified+no_connect"))
    )
    (net (code "71") (name "unconnected-(USB-SW-S1D-Pad14)") (class "Default")
      (node (ref "USB-SW") (pin "14") (pinfunction "S1D_14") (pintype "unspecified+no_connect"))
    )
    (net (code "72") (name "unconnected-(USB-SW-S2C-Pad10)") (class "Default")
      (node (ref "USB-SW") (pin "10") (pinfunction "S2C_10") (pintype "unspecified+no_connect"))
    )
    (net (code "73") (name "unconnected-(USB-SW-S2D-Pad13)") (class "Default")
      (node (ref "USB-SW") (pin "13") (pinfunction "S2D_13") (pintype "unspecified+no_connect"))
    )
  )
)
